# PSRAM.net
KiCad netlist of a schematic drawn in Altium Designer
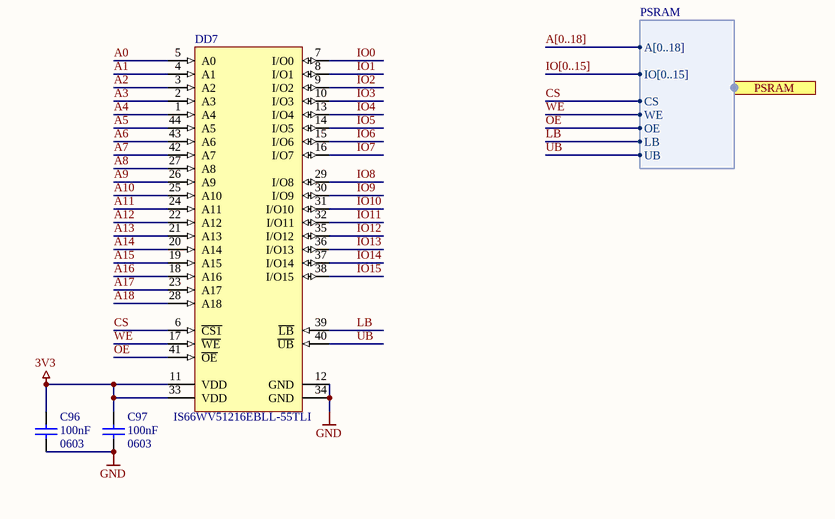
[diagram p0: PSRAM.SchDoc]

(export (version "E")
  (design (tool "Eeschema 10.0.6"))
  (components
    (comp (ref "C96")
      (value "100nF")
      (footprint "CAPC1608L")
      (description "Capacitor ceramic")
      (fields
        (field (name "PACKAGE") "0603")
        (field (name "VOLTAGE") "16V")
        (field (name "Comment") "100nF / 0603 / X7R / 16V")
      )
      (libsource (lib "LED_MAT_3") (part "100nF / 0603 / X7R / 16V"))
    )
    (comp (ref "C97")
      (value "100nF")
      (footprint "CAPC1608L")
      (description "Capacitor ceramic")
      (fields
        (field (name "PACKAGE") "0603")
        (field (name "VOLTAGE") "16V")
        (field (name "Comment") "100nF / 0603 / X7R / 16V")
      )
      (libsource (lib "LED_MAT_3") (part "100nF / 0603 / X7R / 16V"))
    )
    (comp (ref "DD7")
      (value "IS66WV51216EBLL-55TLI")
      (footprint "ISSI-TSOP-2-44_N")
      (fields
        (field (name "MANUFACTURER") "Integrated Silicon Solution Inc (ISSI)")
        (field (name "MANUFACTURER PART NUMBER") "IS66WV51216DBLL-55TLI")
      )
      (libsource (lib "LED_MAT_3") (part "IS66WV51216DBLL-55TLI"))
    )
  )
  (nets
    (net (code "2") (name "/A0") (class "Default")
      (node (ref "DD7") (pin "5") (pinfunction "A0_5") (pintype "input"))
    )
    (net (code "3") (name "/A1") (class "Default")
      (node (ref "DD7") (pin "4") (pinfunction "A1_4") (pintype "input"))
    )
    (net (code "4") (name "/A2") (class "Default")
      (node (ref "DD7") (pin "3") (pinfunction "A2_3") (pintype "input"))
    )
    (net (code "5") (name "/A3") (class "Default")
      (node (ref "DD7") (pin "2") (pinfunction "A3_2") (pintype "input"))
    )
    (net (code "6") (name "/A4") (class "Default")
      (node (ref "DD7") (pin "1") (pinfunction "A4_1") (pintype "input"))
    )
    (net (code "7") (name "/A5") (class "Default")
      (node (ref "DD7") (pin "44") (pinfunction "A5_44") (pintype "input"))
    )
    (net (code "8") (name "/A6") (class "Default")
      (node (ref "DD7") (pin "43") (pinfunction "A6_43") (pintype "input"))
    )
    (net (code "9") (name "/A7") (class "Default")
      (node (ref "DD7") (pin "42") (pinfunction "A7_42") (pintype "input"))
    )
    (net (code "10") (name "/A8") (class "Default")
      (node (ref "DD7") (pin "27") (pinfunction "A8_27") (pintype "input"))
    )
    (net (code "11") (name "/A9") (class "Default")
      (node (ref "DD7") (pin "26") (pinfunction "A9_26") (pintype "input"))
    )
    (net (code "12") (name "/A10") (class "Default")
      (node (ref "DD7") (pin "25") (pinfunction "A10_25") (pintype "input"))
    )
    (net (code "13") (name "/A11") (class "Default")
      (node (ref "DD7") (pin "24") (pinfunction "A11_24") (pintype "input"))
    )
    (net (code "14") (name "/A12") (class "Default")
      (node (ref "DD7") (pin "22") (pinfunction "A12_22") (pintype "input"))
    )
    (net (code "15") (name "/A13") (class "Default")
      (node (ref "DD7") (pin "21") (pinfunction "A13_21") (pintype "input"))
    )
    (net (code "16") (name "/A14") (class "Default")
      (node (ref "DD7") (pin "20") (pinfunction "A14_20") (pintype "input"))
    )
    (net (code "17") (name "/A15") (class "Default")
      (node (ref "DD7") (pin "19") (pinfunction "A15_19") (pintype "input"))
    )
    (net (code "18") (name "/A16") (class "Default")
      (node (ref "DD7") (pin "18") (pinfunction "A16_18") (pintype "input"))
    )
    (net (code "19") (name "/A17") (class "Default")
      (node (ref "DD7") (pin "23") (pinfunction "A17_23") (pintype "input"))
    )
    (net (code "20") (name "/A18") (class "Default")
      (node (ref "DD7") (pin "28") (pinfunction "A18_28") (pintype "input"))
    )
    (net (code "22") (name "/CS") (class "Default")
      (node (ref "DD7") (pin "6") (pinfunction "~{CS1}_6") (pintype "input"))
    )
    (net (code "23") (name "/IO0") (class "Default")
      (node (ref "DD7") (pin "7") (pinfunction "I/O0_7") (pintype "bidirectional"))
    )
    (net (code "24") (name "/IO1") (class "Default")
      (node (ref "DD7") (pin "8") (pinfunction "I/O1_8") (pintype "bidirectional"))
    )
    (net (code "25") (name "/IO2") (class "Default")
      (node (ref "DD7") (pin "9") (pinfunction "I/O2_9") (pintype "bidirectional"))
    )
    (net (code "26") (name "/IO3") (class "Default")
      (node (ref "DD7") (pin "10") (pinfunction "I/O3_10") (pintype "bidirectional"))
    )
    (net (code "27") (name "/IO4") (class "Default")
      (node (ref "DD7") (pin "13") (pinfunction "I/O4_13") (pintype "bidirectional"))
    )
    (net (code "28") (name "/IO5") (class "Default")
      (node (ref "DD7") (pin "14") (pinfunction "I/O5_14") (pintype "bidirectional"))
    )
    (net (code "29") (name "/IO6") (class "Default")
      (node (ref "DD7") (pin "15") (pinfunction "I/O6_15") (pintype "bidirectional"))
    )
    (net (code "30") (name "/IO7") (class "Default")
      (node (ref "DD7") (pin "16") (pinfunction "I/O7_16") (pintype "bidirectional"))
    )
    (net (code "31") (name "/IO8") (class "Default")
      (node (ref "DD7") (pin "29") (pinfunction "I/O8_29") (pintype "bidirectional"))
    )
    (net (code "32") (name "/IO9") (class "Default")
      (node (ref "DD7") (pin "30") (pinfunction "I/O9_30") (pintype "bidirectional"))
    )
    (net (code "33") (name "/IO10") (class "Default")
      (node (ref "DD7") (pin "31") (pinfunction "I/O10_31") (pintype "bidirectional"))
    )
    (net (code "34") (name "/IO11") (class "Default")
      (node (ref "DD7") (pin "32") (pinfunction "I/O11_32") (pintype "bidirectional"))
    )
    (net (code "35") (name "/IO12") (class "Default")
      (node (ref "DD7") (pin "35") (pinfunction "I/O12_35") (pintype "bidirectional"))
    )
    (net (code "36") (name "/IO13") (class "Default")
      (node (ref "DD7") (pin "36") (pinfunction "I/O13_36") (pintype "bidirectional"))
    )
    (net (code "37") (name "/IO14") (class "Default")
      (node (ref "DD7") (pin "37") (pinfunction "I/O14_37") (pintype "bidirectional"))
    )
    (net (code "38") (name "/IO15") (class "Default")
      (node (ref "DD7") (pin "38") (pinfunction "I/O15_38") (pintype "bidirectional"))
    )
    (net (code "39") (name "/LB") (class "Default")
      (node (ref "DD7") (pin "39") (pinfunction "~{LB}_39") (pintype "input"))
    )
    (net (code "40") (name "/OE") (class "Default")
      (node (ref "DD7") (pin "41") (pinfunction "~{OE}_41") (pintype "input"))
    )
    (net (code "42") (name "/UB") (class "Default")
      (node (ref "DD7") (pin "40") (pinfunction "~{UB}_40") (pintype "input"))
    )
    (net (code "43") (name "/WE") (class "Default")
      (node (ref "DD7") (pin "17") (pinfunction "~{WE}_17") (pintype "input"))
    )
    (net (code "45") (name "3V3") (class "Default")
      (node (ref "C96") (pin "2") (pinfunction "2_2") (pintype "passive"))
      (node (ref "C97") (pin "2") (pinfunction "2_2") (pintype "passive"))
      (node (ref "DD7") (pin "11") (pinfunction "VDD_11") (pintype "power_in"))
      (node (ref "DD7") (pin "33") (pinfunction "VDD_33") (pintype "power_in"))
    )
    (net (code "46") (name "GND") (class "Default")
      (node (ref "C96") (pin "1") (pinfunction "1_1") (pintype "passive"))
      (node (ref "C97") (pin "1") (pinfunction "1_1") (pintype "passive"))
      (node (ref "DD7") (pin "12") (pinfunction "GND_12") (pintype "power_in"))
      (node (ref "DD7") (pin "34") (pinfunction "GND_34") (pintype "power_in"))
    )
  )
)
